# H15R80.net
KiCad netlist of a schematic drawn in EAGLE
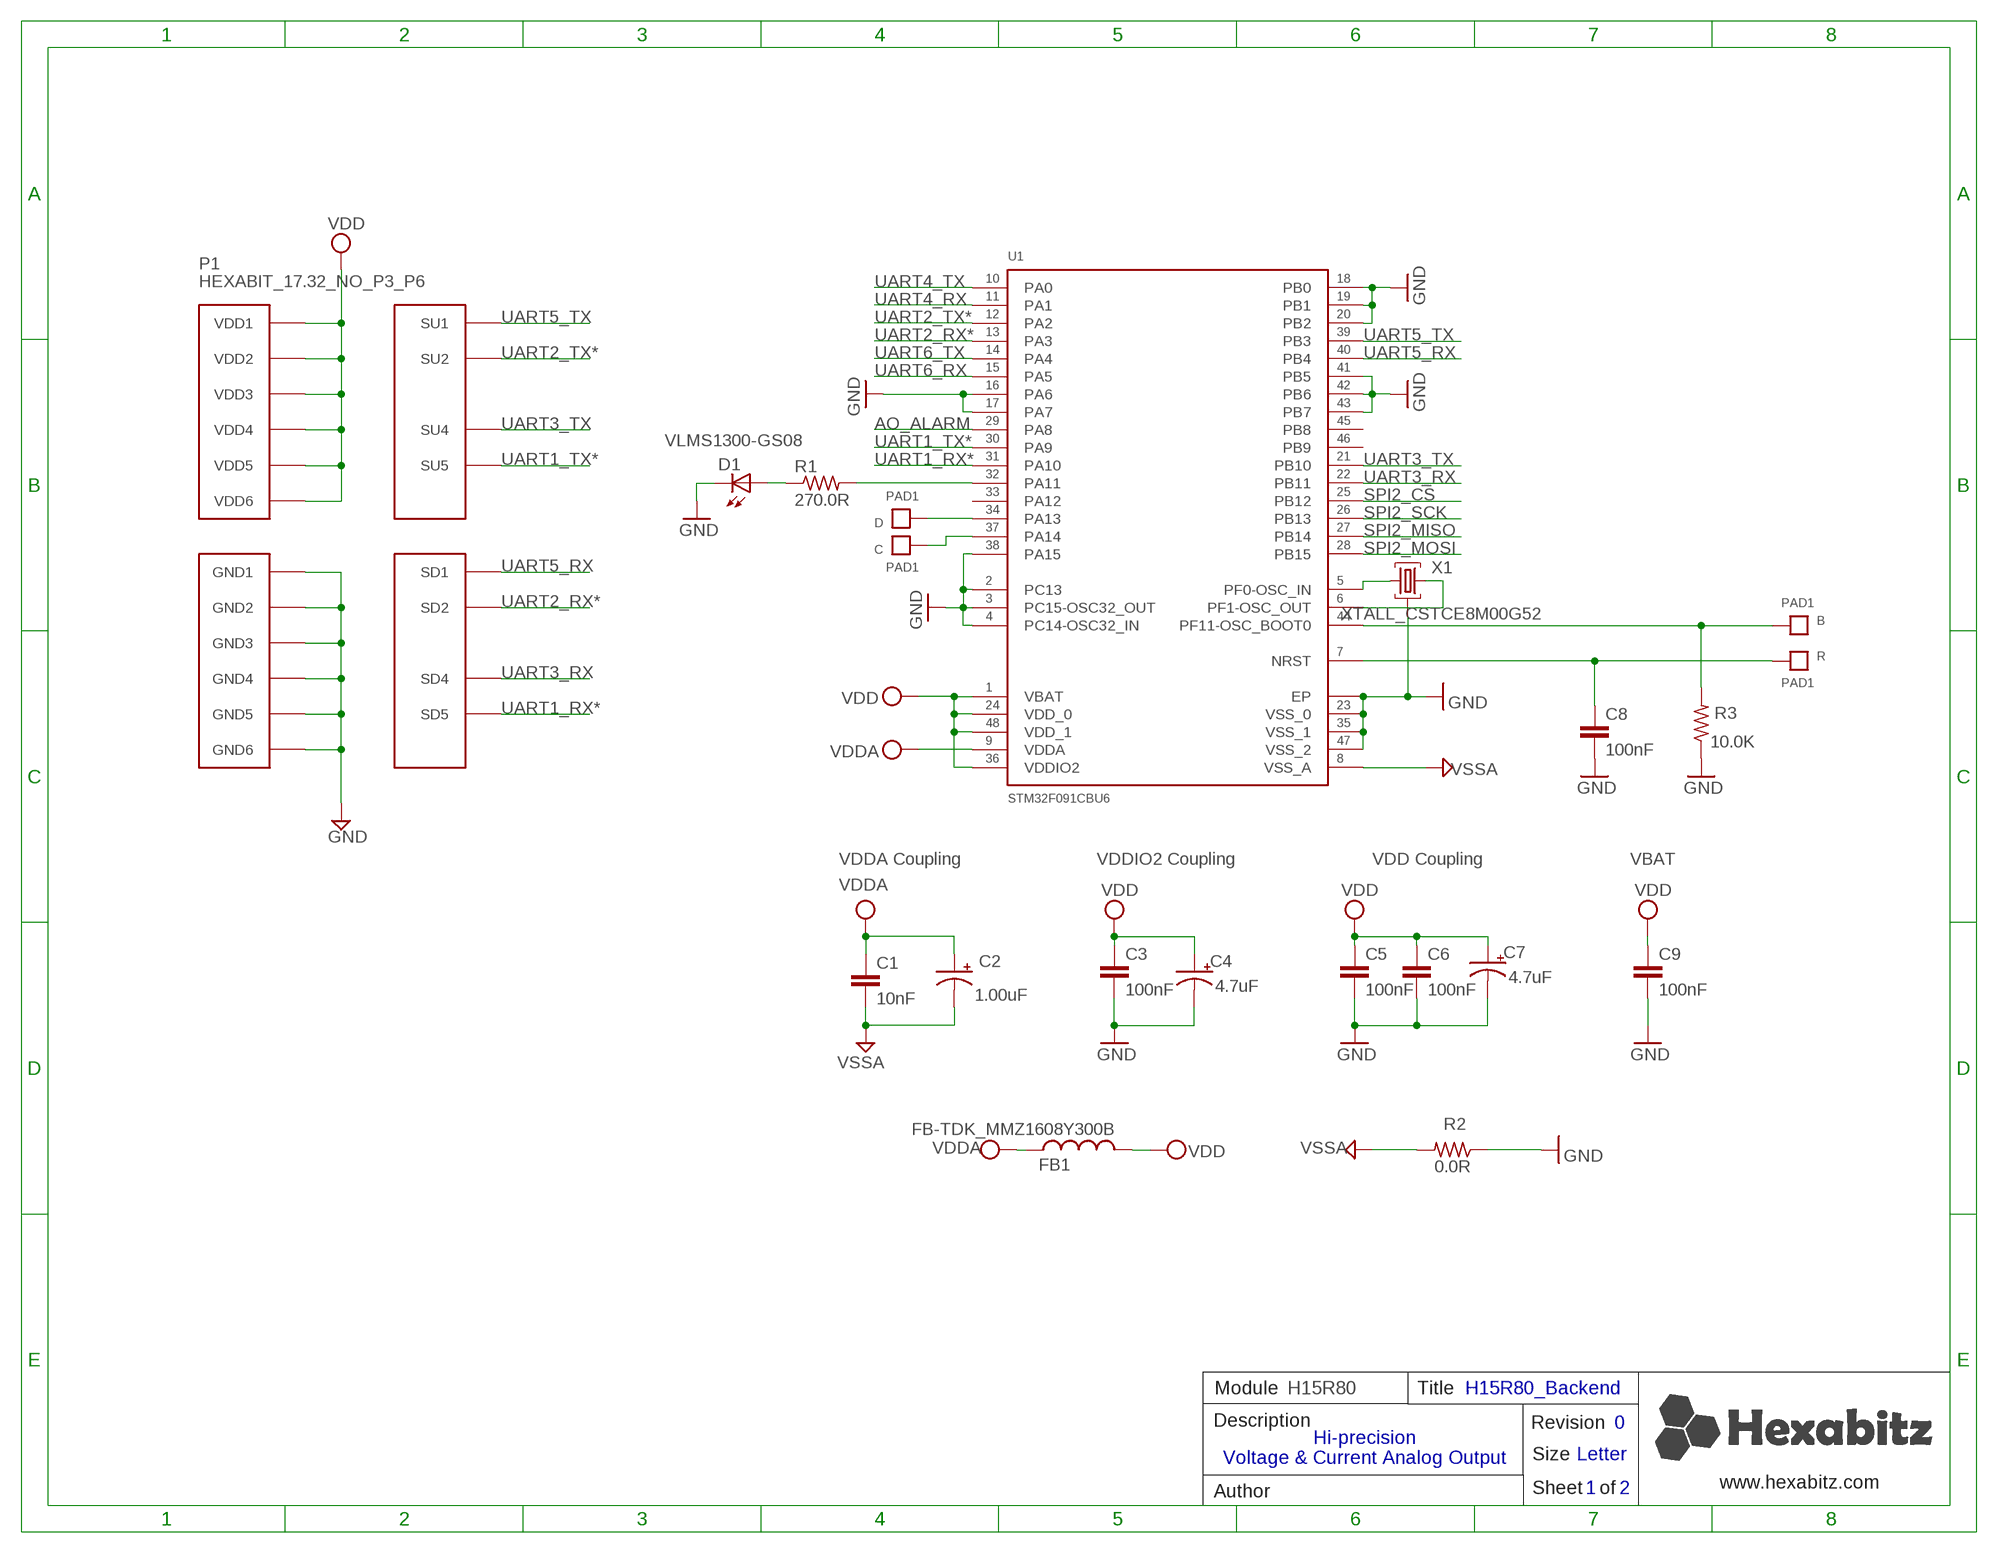
[diagram p0: schematic, sheet 1]
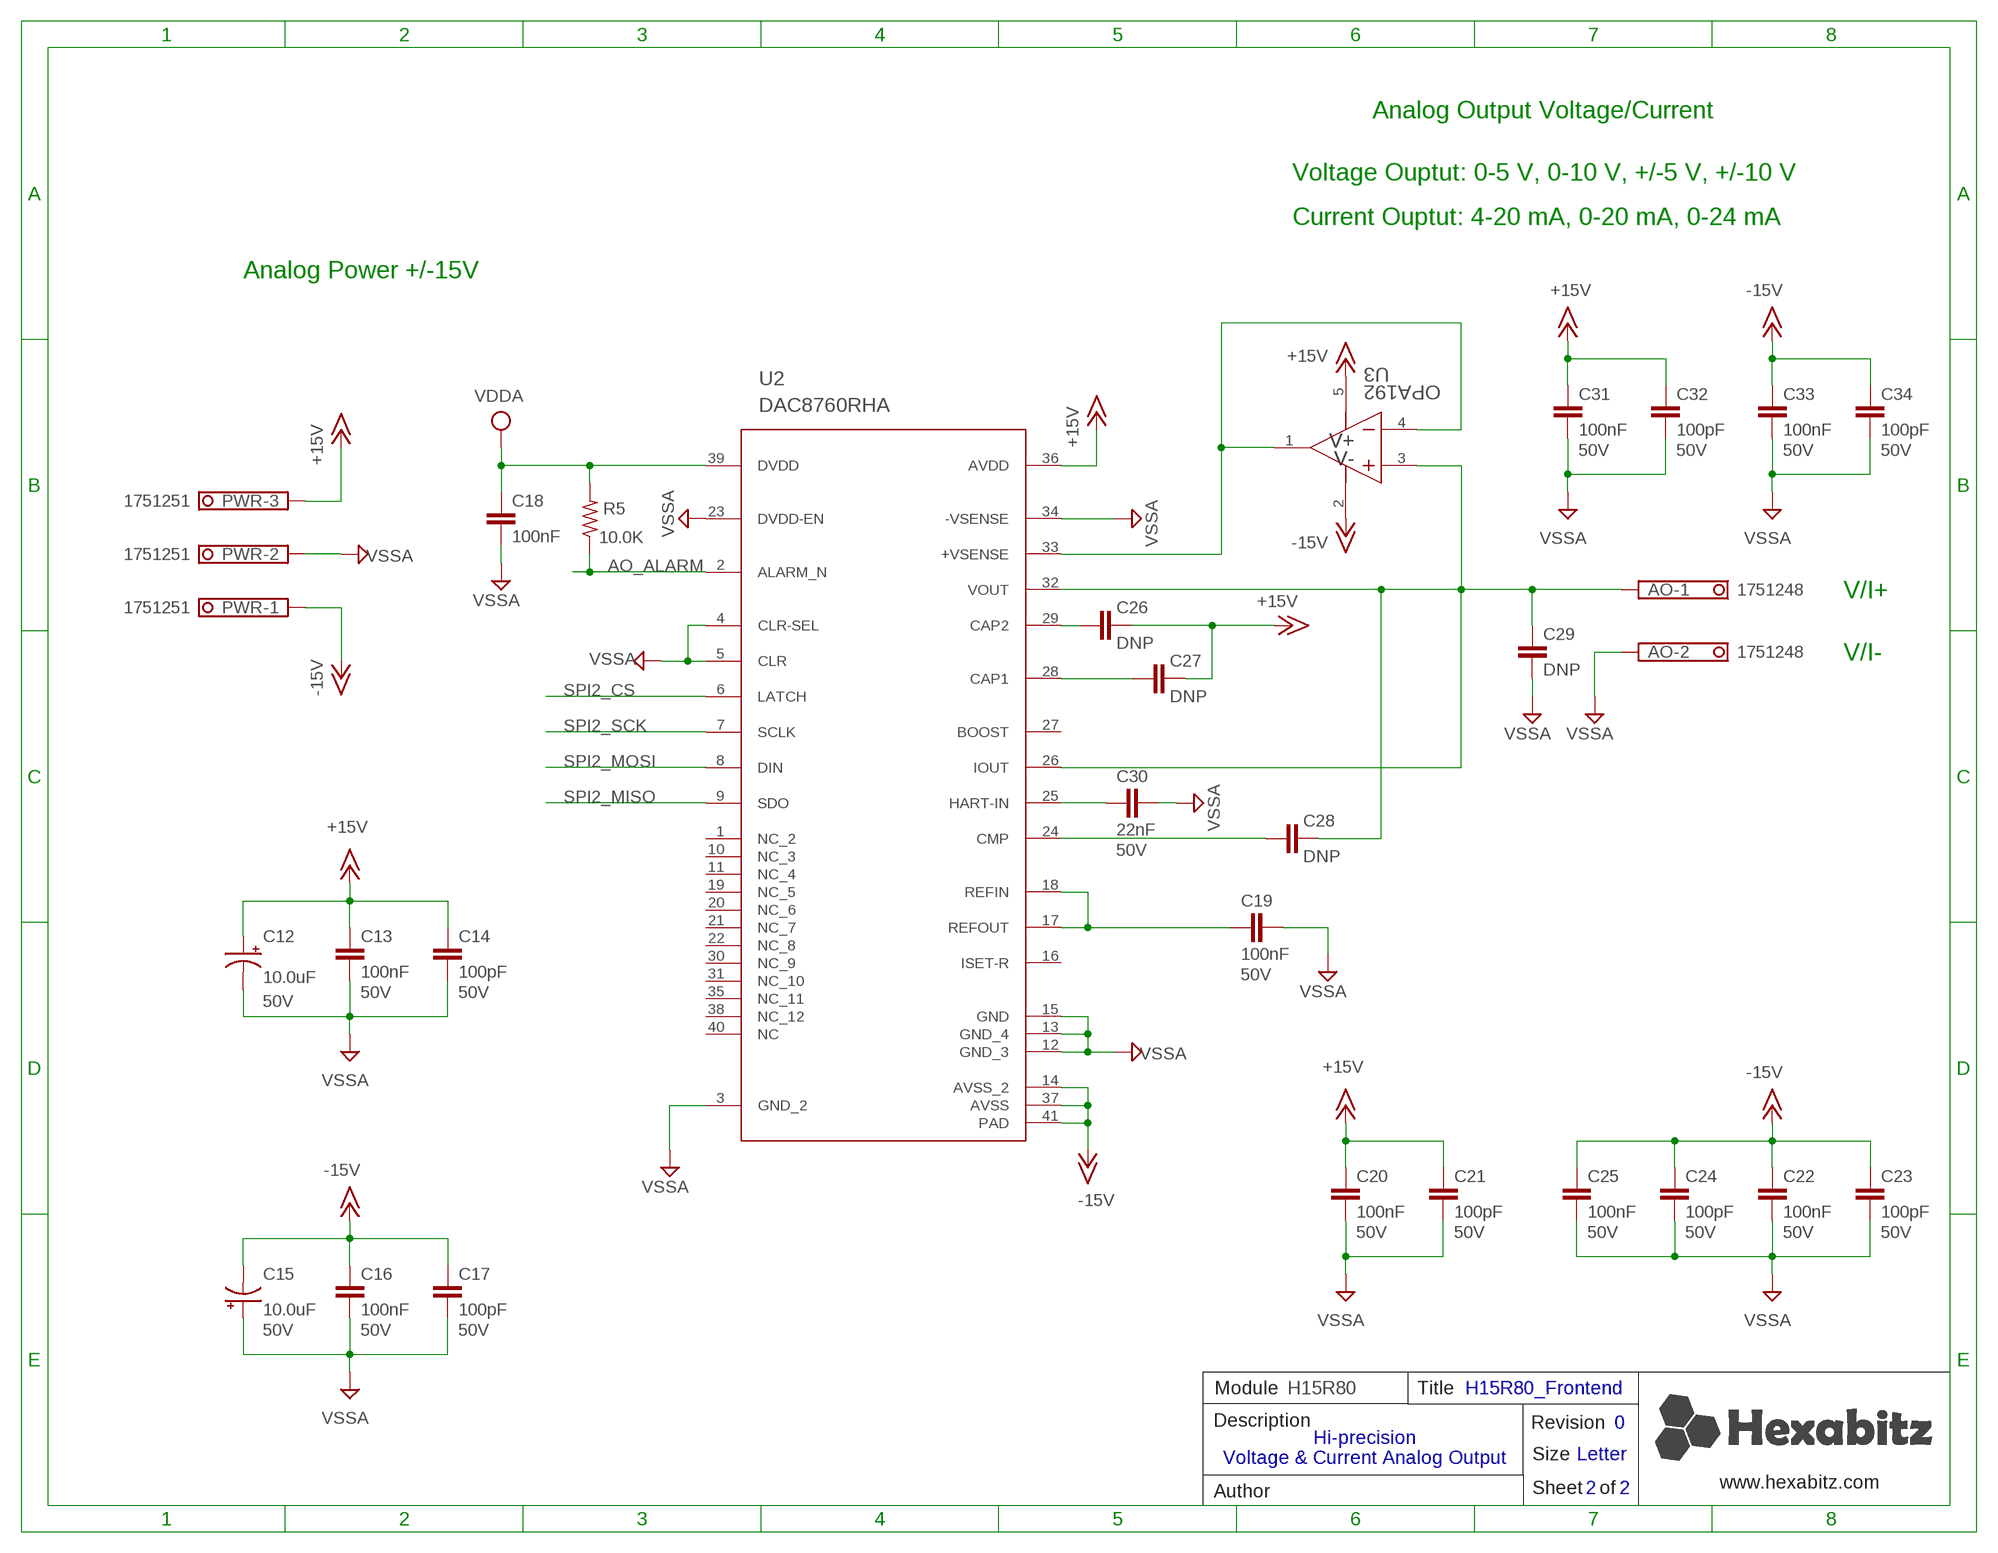
[diagram p1: schematic, sheet 2]

(export (version "E")
  (design (tool "Eeschema 10.0.6"))
  (components
    (comp (ref "B")
      (value "PAD1")
      (footprint "eagle-import:PAD1")
      (libsource (lib "eagle-import") (part "PAD1"))
    )
    (comp (ref "C")
      (value "PAD1")
      (footprint "eagle-import:PAD1")
      (libsource (lib "eagle-import") (part "PAD1"))
    )
    (comp (ref "C1")
      (value "10nF")
      (footprint "eagle-import:C-0603")
      (fields
        (field (name "CAPACITANCE") "10nF")
        (field (name "MFN") "KEMET")
        (field (name "MPN") "C0603C103K5RACTU")
        (field (name "OCTOPART_URL") "https://octopart.com/c0603c103k5ractu-kemet-133094?r=sp&s=R_iPBxLnSmGqhkU2rIMFpg")
        (field (name "TOLERANCE") "10%")
        (field (name "VOLTAGE_RATING") "50V")
      )
      (libsource (lib "eagle-import") (part "C-0603"))
    )
    (comp (ref "C2")
      (value "1.00uF")
      (footprint "eagle-import:C-0805-POL")
      (fields
        (field (name "CAPACITANCE") "1.00uF")
        (field (name "MFN") "Yageo")
        (field (name "MPN") "CC0805KKX7R7BB105")
        (field (name "OCTOPART_URL") "https://octopart.com/cc0805kkx7r7bb105-yageo-8376555?r=sp&s=YKl1wwtkROau_X5nniH2ig")
        (field (name "TOLERANCE") "10%")
        (field (name "VOLTAGE_RATING") "16V")
      )
      (libsource (lib "eagle-import") (part "C-0805-POL"))
    )
    (comp (ref "C3")
      (value "100nF")
      (footprint "eagle-import:C-0603")
      (fields
        (field (name "CAPACITANCE") "100nF")
        (field (name "MFN") "KEMET")
        (field (name "MPN") "C0603C104K8RACTU")
        (field (name "OCTOPART_URL") "https://octopart.com/c0603c104k8ractu-kemet-145075?r=sp&s=9bS9ASSwSEqMCE9KBEQZ0g")
        (field (name "TOLERANCE") "10%")
        (field (name "VOLTAGE_RATING") "10V")
      )
      (libsource (lib "eagle-import") (part "C-0603"))
    )
    (comp (ref "C4")
      (value "4.7uF")
      (footprint "eagle-import:C-0805-POL")
      (fields
        (field (name "CAPACITANCE") "4.7uF")
        (field (name "MFN") "Murata")
        (field (name "MPN") "GRM21BC81E475KA12L")
        (field (name "OCTOPART_URL") "https://octopart.com/grm21bc81e475ka12l-murata-10331911?r=sp&s=RY3qZSD8T6mG6TC9CHI5qQ")
        (field (name "TOLERANCE") "10%")
        (field (name "VOLTAGE_RATING") "25V")
      )
      (libsource (lib "eagle-import") (part "C-0805-POL"))
    )
    (comp (ref "C5")
      (value "100nF")
      (footprint "eagle-import:C-0603")
      (fields
        (field (name "CAPACITANCE") "100nF")
        (field (name "MFN") "KEMET")
        (field (name "MPN") "C0603C104K8RACTU")
        (field (name "OCTOPART_URL") "https://octopart.com/c0603c104k8ractu-kemet-145075?r=sp&s=9bS9ASSwSEqMCE9KBEQZ0g")
        (field (name "TOLERANCE") "10%")
        (field (name "VOLTAGE_RATING") "10")
      )
      (libsource (lib "eagle-import") (part "C-0603"))
    )
    (comp (ref "C6")
      (value "100nF")
      (footprint "eagle-import:C-0603")
      (fields
        (field (name "CAPACITANCE") "100nF")
        (field (name "MFN") "KEMET")
        (field (name "MPN") "C0603C104K8RACTU")
        (field (name "OCTOPART_URL") "https://octopart.com/c0603c104k8ractu-kemet-145075?r=sp&s=9bS9ASSwSEqMCE9KBEQZ0g")
        (field (name "TOLERANCE") "10%")
        (field (name "VOLTAGE_RATING") "10V")
      )
      (libsource (lib "eagle-import") (part "C-0603"))
    )
    (comp (ref "C7")
      (value "4.7uF")
      (footprint "eagle-import:C-0805-POL")
      (fields
        (field (name "CAPACITANCE") "4.7uF")
        (field (name "MFN") "Murata")
        (field (name "MPN") "GRM21BC81E475KA12L")
        (field (name "OCTOPART_URL") "https://octopart.com/grm21bc81e475ka12l-murata-10331911?r=sp&s=RY3qZSD8T6mG6TC9CHI5qQ")
        (field (name "TOLERANCE") "10%")
        (field (name "VOLTAGE_RATING") "25V")
      )
      (libsource (lib "eagle-import") (part "C-0805-POL"))
    )
    (comp (ref "C8")
      (value "100nF")
      (footprint "eagle-import:C-0603")
      (fields
        (field (name "CAPACITANCE") "100nF")
        (field (name "MFN") "KEMET")
        (field (name "MPN") "C0603C104K8RACTU")
        (field (name "OCTOPART_URL") "https://octopart.com/c0603c104k8ractu-kemet-145075?r=sp&s=9bS9ASSwSEqMCE9KBEQZ0g")
        (field (name "TOLERANCE") "10%")
        (field (name "VOLTAGE_RATING") "10V")
      )
      (libsource (lib "eagle-import") (part "C-0603"))
    )
    (comp (ref "C9")
      (value "100nF")
      (footprint "eagle-import:C-0603")
      (fields
        (field (name "CAPACITANCE") "100nF")
        (field (name "MFN") "KEMET")
        (field (name "MPN") "C0603C104K8RACTU")
        (field (name "OCTOPART_URL") "https://octopart.com/c0603c104k8ractu-kemet-145075?r=sp&s=9bS9ASSwSEqMCE9KBEQZ0g")
        (field (name "TOLERANCE") "10V")
        (field (name "VOLTAGE_RATING") "10%")
      )
      (libsource (lib "eagle-import") (part "C-0603"))
    )
    (comp (ref "D")
      (value "PAD1")
      (footprint "eagle-import:PAD1")
      (libsource (lib "eagle-import") (part "PAD1"))
    )
    (comp (ref "D1")
      (value "VLMS1300-GS08")
      (footprint "eagle-import:VLMS1300-GS08")
      (fields
        (field (name "MFN") "Vishay")
        (field (name "MPN") "VLMS1300-GS08")
        (field (name "OCTOPART_URL") "https://octopart.com/vlms1300-gs08-vishay-21709201?r=sp&s=_gcP4_q8T1SC6PJQPTQ9yA")
      )
      (libsource (lib "eagle-import") (part "VLMS1300-GS08"))
    )
    (comp (ref "FB1")
      (value "FB-TDK_MMZ1608Y300B")
      (footprint "eagle-import:FB-TDK_MMZ1608Y300B")
      (fields
        (field (name "MFN") "TDK ")
        (field (name "MPN") "MMZ1608Y300B")
        (field (name "OCTOPART_URL") "https://octopart.com/mmz1608y300b-tdk-368280?r=sp&s=cd9_2ZEqQ9q9UNBuQgHAiA")
      )
      (libsource (lib "eagle-import") (part "FB-TDK_MMZ1608Y300B"))
    )
    (comp (ref "P1")
      (value "HEXABIT_17.32_NO_P3_P6")
      (footprint "eagle-import:HEXABIT_17.32_NO_P3_P6")
      (libsource (lib "eagle-import") (part "HEXABIT_?_NO_P3_P617.32"))
    )
    (comp (ref "R")
      (value "PAD1")
      (footprint "eagle-import:PAD1")
      (libsource (lib "eagle-import") (part "PAD1"))
    )
    (comp (ref "R1")
      (value "270.0R")
      (footprint "eagle-import:R-0603")
      (fields
        (field (name "MFN") "Yageo")
        (field (name "MPN") "RC0603FR-07270RL")
        (field (name "OCTOPART_URL") "https://octopart.com/search?q=RC0603FR-07270RL&start=0")
        (field (name "RESISTANCE") "270.0 Ohm")
        (field (name "TOLERANCE") "1%")
      )
      (libsource (lib "eagle-import") (part "R-0603"))
    )
    (comp (ref "R2")
      (value "0.0R")
      (footprint "eagle-import:R-0603")
      (fields
        (field (name "MFN") "Yageo")
        (field (name "MPN") "RC0603JR-070RL")
        (field (name "OCTOPART_URL") "https://octopart.com/rc0603jr-070rl-yageo-1241539?r=sp&s=X2NteqRjRNWrnx42Y0aliA")
        (field (name "RESISTANCE") "0.0 Ohm")
      )
      (libsource (lib "eagle-import") (part "R-0603"))
    )
    (comp (ref "R3")
      (value "10.0K")
      (footprint "eagle-import:R-0603")
      (fields
        (field (name "MFN") "Yageo")
        (field (name "MPN") "RC0603JR-0710KL")
        (field (name "OCTOPART_URL") "https://octopart.com/search?q=RC0603JR-0710KL&start=0")
        (field (name "RESISTANCE") "10.0K Ohm")
        (field (name "TOLERANCE") "5%")
      )
      (libsource (lib "eagle-import") (part "R-0603"))
    )
    (comp (ref "U1")
      (value "STM32F091CBU6")
      (footprint "eagle-import:STM32F091CBU6")
      (libsource (lib "eagle-import") (part "STM32F091CBU6"))
    )
    (comp (ref "X1")
      (value "XTALL_CSTCE8M00G52")
      (footprint "eagle-import:XTALL_CSTCE8M00G52")
      (fields (field (name "MPN") "CSTCE8M00G52Z-R0"))
      (libsource (lib "eagle-import") (part "XTALL_CSTCE8M00G52"))
    )
    (comp (ref "AO")
      (value "1751248")
      (footprint "eagle-import:1751248")
      (fields
        (field (name "MPN") "1751248")
        (field (name "MFN") "Phoenix Contact")
        (field (name "OCTOPART_URL") "https://octopart.com/1751248-phoenix+contact-31334?r=sp&s=dfbEyNHiQNetUL69ahOrPQ ")
      )
      (libsource (lib "eagle-import") (part "1751248"))
    )
    (comp (ref "C12")
      (value "10.0uF")
      (footprint "eagle-import:CT7343")
      (fields (field (name "MPN") "T491D106K050AT") (field (name "VOLTAGE") "50V"))
      (libsource (lib "eagle-import") (part "CPOL-USCT7343"))
    )
    (comp (ref "C13")
      (value "100nF")
      (footprint "eagle-import:C-0603")
      (fields
        (field (name "CAPACITANCE") "100nF")
        (field (name "MFN") "Samsung")
        (field (name "MPN") "CL10B104KB8NNNC")
        (field (name "OCTOPART_URL") "https://octopart.com/cl10b104kb8nnnc-samsung-7928277?r=sp&s=fIKkgin8S22eXTUxF1gXsw")
        (field (name "TOLERANCE") "10%")
        (field (name "VOLTAGE_RATING") "50V")
      )
      (libsource (lib "eagle-import") (part "C-0603"))
    )
    (comp (ref "C14")
      (value "100pF")
      (footprint "eagle-import:C-0603")
      (fields
        (field (name "CAPACITANCE") "100pF")
        (field (name "MFN") "Avx")
        (field (name "MPN") "06035A101JAT2A")
        (field (name "OCTOPART_URL") "https://octopart.com/06035a101jat2a-avx-55386344?r=sp&s=WDfgRo-ITV2A4U5JT5ZyKQ")
        (field (name "TOLERANCE") "10%")
        (field (name "VOLTAGE_RATING") "50V")
      )
      (libsource (lib "eagle-import") (part "C-0603"))
    )
    (comp (ref "C15")
      (value "10.0uF")
      (footprint "eagle-import:CT7343")
      (fields (field (name "MPN") "T491D106K050AT") (field (name "VOLTAGE") "50V"))
      (libsource (lib "eagle-import") (part "CPOL-USCT7343"))
    )
    (comp (ref "C16")
      (value "100nF")
      (footprint "eagle-import:C-0603")
      (fields
        (field (name "CAPACITANCE") "100nF")
        (field (name "MFN") "Samsung")
        (field (name "MPN") "CL10B104KB8NNNC")
        (field (name "OCTOPART_URL") "https://octopart.com/cl10b104kb8nnnc-samsung-7928277?r=sp&s=fIKkgin8S22eXTUxF1gXsw")
        (field (name "TOLERANCE") "10%")
        (field (name "VOLTAGE_RATING") "50V")
      )
      (libsource (lib "eagle-import") (part "C-0603"))
    )
    (comp (ref "C17")
      (value "100pF")
      (footprint "eagle-import:C-0603")
      (fields
        (field (name "CAPACITANCE") "100pF")
        (field (name "MFN") "Avx")
        (field (name "MPN") "06035A101JAT2A")
        (field (name "OCTOPART_URL") "https://octopart.com/06035a101jat2a-avx-55386344?r=sp&s=WDfgRo-ITV2A4U5JT5ZyKQ")
        (field (name "TOLERANCE") "10%")
        (field (name "VOLTAGE_RATING") "50V")
      )
      (libsource (lib "eagle-import") (part "C-0603"))
    )
    (comp (ref "C18")
      (value "100nF")
      (footprint "eagle-import:C-0603")
      (fields
        (field (name "CAPACITANCE") "100nF")
        (field (name "MFN") "KEMET")
        (field (name "MPN") "C0603C104K8RACTU")
        (field (name "OCTOPART_URL") "https://octopart.com/c0603c104k8ractu-kemet-145075?r=sp&s=9bS9ASSwSEqMCE9KBEQZ0g")
        (field (name "TOLERANCE") "10%")
        (field (name "VOLTAGE_RATING") "10V")
      )
      (libsource (lib "eagle-import") (part "C-0603"))
    )
    (comp (ref "C19")
      (value "100nF")
      (footprint "eagle-import:C-0603")
      (fields
        (field (name "CAPACITANCE") "100nF")
        (field (name "MFN") "Samsung")
        (field (name "MPN") "CL10B104KB8NNNC")
        (field (name "OCTOPART_URL") "https://octopart.com/cl10b104kb8nnnc-samsung-7928277?r=sp&s=fIKkgin8S22eXTUxF1gXsw")
        (field (name "TOLERANCE") "10%")
        (field (name "VOLTAGE_RATING") "50V")
      )
      (libsource (lib "eagle-import") (part "C-0603"))
    )
    (comp (ref "C20")
      (value "100nF")
      (footprint "eagle-import:C-0603")
      (fields
        (field (name "CAPACITANCE") "100nF")
        (field (name "MFN") "Samsung")
        (field (name "MPN") "CL10B104KB8NNNC")
        (field (name "OCTOPART_URL") "https://octopart.com/cl10b104kb8nnnc-samsung-7928277?r=sp&s=fIKkgin8S22eXTUxF1gXsw")
        (field (name "TOLERANCE") "10%")
        (field (name "VOLTAGE_RATING") "50V")
      )
      (libsource (lib "eagle-import") (part "C-0603"))
    )
    (comp (ref "C21")
      (value "100pF")
      (footprint "eagle-import:C-0603")
      (fields
        (field (name "CAPACITANCE") "100pF")
        (field (name "MFN") "Avx")
        (field (name "MPN") "06035A101JAT2A")
        (field (name "OCTOPART_URL") "https://octopart.com/06035a101jat2a-avx-55386344?r=sp&s=WDfgRo-ITV2A4U5JT5ZyKQ")
        (field (name "TOLERANCE") "10%")
        (field (name "VOLTAGE_RATING") "50V")
      )
      (libsource (lib "eagle-import") (part "C-0603"))
    )
    (comp (ref "C22")
      (value "100nF")
      (footprint "eagle-import:C-0603")
      (fields
        (field (name "CAPACITANCE") "100nF")
        (field (name "MFN") "Samsung")
        (field (name "MPN") "CL10B104KB8NNNC")
        (field (name "OCTOPART_URL") "https://octopart.com/cl10b104kb8nnnc-samsung-7928277?r=sp&s=fIKkgin8S22eXTUxF1gXsw")
        (field (name "TOLERANCE") "10%")
        (field (name "VOLTAGE_RATING") "50V")
      )
      (libsource (lib "eagle-import") (part "C-0603"))
    )
    (comp (ref "C23")
      (value "100pF")
      (footprint "eagle-import:C-0603")
      (fields
        (field (name "CAPACITANCE") "100pF")
        (field (name "MFN") "Avx")
        (field (name "MPN") "06035A101JAT2A")
        (field (name "OCTOPART_URL") "https://octopart.com/06035a101jat2a-avx-55386344?r=sp&s=WDfgRo-ITV2A4U5JT5ZyKQ")
        (field (name "TOLERANCE") "10%")
        (field (name "VOLTAGE_RATING") "50V")
      )
      (libsource (lib "eagle-import") (part "C-0603"))
    )
    (comp (ref "C24")
      (value "100pF")
      (footprint "eagle-import:C-0603")
      (fields
        (field (name "CAPACITANCE") "100pF")
        (field (name "MFN") "Avx")
        (field (name "MPN") "06035A101JAT2A")
        (field (name "OCTOPART_URL") "https://octopart.com/06035a101jat2a-avx-55386344?r=sp&s=WDfgRo-ITV2A4U5JT5ZyKQ")
        (field (name "TOLERANCE") "10%")
        (field (name "VOLTAGE_RATING") "50V")
      )
      (libsource (lib "eagle-import") (part "C-0603"))
    )
    (comp (ref "C25")
      (value "100nF")
      (footprint "eagle-import:C-0603")
      (fields
        (field (name "CAPACITANCE") "100nF")
        (field (name "MFN") "Samsung")
        (field (name "MPN") "CL10B104KB8NNNC")
        (field (name "OCTOPART_URL") "https://octopart.com/cl10b104kb8nnnc-samsung-7928277?r=sp&s=fIKkgin8S22eXTUxF1gXsw")
        (field (name "TOLERANCE") "10%")
        (field (name "VOLTAGE_RATING") "50V")
      )
      (libsource (lib "eagle-import") (part "C-0603"))
    )
    (comp (ref "C26")
      (value "DNP")
      (footprint "eagle-import:C-0603")
      (fields (field (name "CAPACITANCE") "DNP") (field (name "MPN") "DNP"))
      (libsource (lib "eagle-import") (part "C-0603"))
    )
    (comp (ref "C27")
      (value "DNP")
      (footprint "eagle-import:C-0603")
      (fields (field (name "CAPACITANCE") "DNP") (field (name "MPN") "DNP"))
      (libsource (lib "eagle-import") (part "C-0603"))
    )
    (comp (ref "C28")
      (value "DNP")
      (footprint "eagle-import:C-0603")
      (fields (field (name "CAPACITANCE") "DNP") (field (name "MPN") "DNP"))
      (libsource (lib "eagle-import") (part "C-0603"))
    )
    (comp (ref "C29")
      (value "DNP")
      (footprint "eagle-import:C-0603")
      (fields (field (name "CAPACITANCE") "DNP") (field (name "MPN") "DNP"))
      (libsource (lib "eagle-import") (part "C-0603"))
    )
    (comp (ref "C30")
      (value "22nF")
      (footprint "eagle-import:C-0603")
      (fields
        (field (name "CAPACITANCE") "22nF")
        (field (name "MFN") "TDK")
        (field (name "MPN") "C1608X7R1H223K080AA")
        (field (name "OCTOPART_URL") "https://octopart.com/c1608x7r1h223k080aa-tdk-25947667?r=sp&s=T8cT_uRxS7ewuHBmxCxszg")
        (field (name "TOLERANCE") "10%")
        (field (name "VOLTAGE_RATING") "50V")
      )
      (libsource (lib "eagle-import") (part "C-0603"))
    )
    (comp (ref "C31")
      (value "100nF")
      (footprint "eagle-import:C-0603")
      (fields
        (field (name "CAPACITANCE") "100nF")
        (field (name "MFN") "Samsung")
        (field (name "MPN") "CL10B104KB8NNNC")
        (field (name "OCTOPART_URL") "https://octopart.com/cl10b104kb8nnnc-samsung-7928277?r=sp&s=fIKkgin8S22eXTUxF1gXsw")
        (field (name "TOLERANCE") "10%")
        (field (name "VOLTAGE_RATING") "50V")
      )
      (libsource (lib "eagle-import") (part "C-0603"))
    )
    (comp (ref "C32")
      (value "100pF")
      (footprint "eagle-import:C-0603")
      (fields
        (field (name "CAPACITANCE") "100pF")
        (field (name "MFN") "Avx")
        (field (name "MPN") "06035A101JAT2A")
        (field (name "OCTOPART_URL") "https://octopart.com/06035a101jat2a-avx-55386344?r=sp&s=WDfgRo-ITV2A4U5JT5ZyKQ")
        (field (name "TOLERANCE") "10%")
        (field (name "VOLTAGE_RATING") "50V")
      )
      (libsource (lib "eagle-import") (part "C-0603"))
    )
    (comp (ref "C33")
      (value "100nF")
      (footprint "eagle-import:C-0603")
      (fields
        (field (name "CAPACITANCE") "100nF")
        (field (name "MFN") "Samsung")
        (field (name "MPN") "CL10B104KB8NNNC")
        (field (name "OCTOPART_URL") "https://octopart.com/cl10b104kb8nnnc-samsung-7928277?r=sp&s=fIKkgin8S22eXTUxF1gXsw")
        (field (name "TOLERANCE") "10%")
        (field (name "VOLTAGE_RATING") "50V")
      )
      (libsource (lib "eagle-import") (part "C-0603"))
    )
    (comp (ref "C34")
      (value "100pF")
      (footprint "eagle-import:C-0603")
      (fields
        (field (name "CAPACITANCE") "100pF")
        (field (name "MFN") "Avx")
        (field (name "MPN") "06035A101JAT2A")
        (field (name "OCTOPART_URL") "https://octopart.com/06035a101jat2a-avx-55386344?r=sp&s=WDfgRo-ITV2A4U5JT5ZyKQ")
        (field (name "TOLERANCE") "10%")
        (field (name "VOLTAGE_RATING") "50V")
      )
      (libsource (lib "eagle-import") (part "C-0603"))
    )
    (comp (ref "PWR")
      (value "1751251")
      (footprint "eagle-import:1751251")
      (fields
        (field (name "MFN") "Phoenix Contact")
        (field (name "MPN") "1751251")
        (field (name "OCTOPART_URL") "https://octopart.com/1751251-phoenix+contact-36473?r=sp&s=9M0VWNoHTyq04j3qI6lQOQ ")
      )
      (libsource (lib "eagle-import") (part "1751251"))
    )
    (comp (ref "R5")
      (value "10.0K")
      (footprint "eagle-import:R-0603")
      (fields
        (field (name "MFN") "Yageo")
        (field (name "MPN") "RC0603JR-0710KL")
        (field (name "OCTOPART_URL") "https://octopart.com/search?q=RC0603JR-0710KL&start=0")
        (field (name "RESISTANCE") "10.0K Ohm")
        (field (name "TOLERANCE") "5%")
      )
      (libsource (lib "eagle-import") (part "R-0603"))
    )
    (comp (ref "U2")
      (value "DAC8760RHA")
      (footprint "eagle-import:RHA0040A")
      (fields
        (field (name "MANUFACTURER") "Texas Instruments")
        (field (name "MPN") "DAC8760IRHAR")
        (field (name "PARTNUMBER") "DAC7760IRHAR")
      )
      (libsource (lib "eagle-import") (part "DAC7760IRHAR"))
    )
    (comp (ref "U3")
      (value "OPA192")
      (footprint "eagle-import:DBV0005A_N")
      (fields
        (field (name "ALTERNATE_PARTNUMBER") "OPA192IDBVT")
        (field (name "MANUFACTURER") "Texas Instruments")
        (field (name "PARTNUMBER") "OPA192IDBVR")
      )
      (libsource (lib "eagle-import") (part "OPA192IDBVR"))
    )
  )
  (nets
    (net (code "1") (name "+15V") (class "Default")
      (node (ref "C12") (pin "+") (pinfunction "+_+") (pintype "passive"))
      (node (ref "C13") (pin "1") (pinfunction "1_1") (pintype "passive"))
      (node (ref "C14") (pin "1") (pinfunction "1_1") (pintype "passive"))
      (node (ref "C20") (pin "1") (pinfunction "1_1") (pintype "passive"))
      (node (ref "C21") (pin "1") (pinfunction "1_1") (pintype "passive"))
      (node (ref "C26") (pin "2") (pinfunction "2_2") (pintype "passive"))
      (node (ref "C27") (pin "2") (pinfunction "2_2") (pintype "passive"))
      (node (ref "C31") (pin "1") (pinfunction "1_1") (pintype "passive"))
      (node (ref "C32") (pin "1") (pinfunction "1_1") (pintype "passive"))
      (node (ref "PWR") (pin "3") (pinfunction "K_3") (pintype "passive"))
      (node (ref "U2") (pin "36") (pinfunction "AVDD_36") (pintype "power_in"))
      (node (ref "U3") (pin "5") (pinfunction "V+_5") (pintype "power_in"))
    )
    (net (code "2") (name "-15V") (class "Default")
      (node (ref "C15") (pin "-") (pinfunction "-_-") (pintype "passive"))
      (node (ref "C16") (pin "1") (pinfunction "1_1") (pintype "passive"))
      (node (ref "C17") (pin "1") (pinfunction "1_1") (pintype "passive"))
      (node (ref "C22") (pin "1") (pinfunction "1_1") (pintype "passive"))
      (node (ref "C23") (pin "1") (pinfunction "1_1") (pintype "passive"))
      (node (ref "C24") (pin "1") (pinfunction "1_1") (pintype "passive"))
      (node (ref "C25") (pin "1") (pinfunction "1_1") (pintype "passive"))
      (node (ref "C33") (pin "1") (pinfunction "1_1") (pintype "passive"))
      (node (ref "C34") (pin "1") (pinfunction "1_1") (pintype "passive"))
      (node (ref "PWR") (pin "1") (pinfunction "K_1") (pintype "passive"))
      (node (ref "U2") (pin "14") (pinfunction "AVSS_2_14") (pintype "power_in"))
      (node (ref "U2") (pin "37") (pinfunction "AVSS_37") (pintype "power_in"))
      (node (ref "U2") (pin "41") (pinfunction "PAD_41") (pintype "power_in"))
      (node (ref "U3") (pin "2") (pinfunction "V-_2") (pintype "power_in"))
    )
    (net (code "3") (name "AO_ALARM") (class "Default")
      (node (ref "R5") (pin "1") (pinfunction "1_1") (pintype "passive"))
      (node (ref "U1") (pin "P$29") (pinfunction "PA8_P$29") (pintype "bidirectional"))
      (node (ref "U2") (pin "2") (pinfunction "ALARM_N_2") (pintype "open_collector"))
    )
    (net (code "4") (name "GND") (class "Default")
      (node (ref "C3") (pin "2") (pinfunction "2_2") (pintype "passive"))
      (node (ref "C4") (pin "2") (pinfunction "-_2") (pintype "passive"))
      (node (ref "C5") (pin "2") (pinfunction "2_2") (pintype "passive"))
      (node (ref "C6") (pin "2") (pinfunction "2_2") (pintype "passive"))
      (node (ref "C7") (pin "2") (pinfunction "-_2") (pintype "passive"))
      (node (ref "C8") (pin "2") (pinfunction "2_2") (pintype "passive"))
      (node (ref "C9") (pin "2") (pinfunction "2_2") (pintype "passive"))
      (node (ref "D1") (pin "C") (pinfunction "C_C") (pintype "passive"))
      (node (ref "P1") (pin "PAD_PD10") (pinfunction "GND4_PAD_PD10") (pintype "power_in"))
      (node (ref "P1") (pin "PAD_PD11") (pinfunction "GND5_PAD_PD11") (pintype "power_in"))
      (node (ref "P1") (pin "PAD_PD12") (pinfunction "GND6_PAD_PD12") (pintype "power_in"))
      (node (ref "P1") (pin "PAD_PD7") (pinfunction "GND1_PAD_PD7") (pintype "power_in"))
      (node (ref "P1") (pin "PAD_PD8") (pinfunction "GND2_PAD_PD8") (pintype "power_in"))
      (node (ref "P1") (pin "PAD_PD9") (pinfunction "GND3_PAD_PD9") (pintype "power_in"))
      (node (ref "R2") (pin "1") (pinfunction "1_1") (pintype "passive"))
      (node (ref "R3") (pin "1") (pinfunction "1_1") (pintype "passive"))
      (node (ref "U1") (pin "EP") (pinfunction "EP_EP") (pintype "power_in"))
      (node (ref "U1") (pin "P$16") (pinfunction "PA6_P$16") (pintype "bidirectional"))
      (node (ref "U1") (pin "P$17") (pinfunction "PA7_P$17") (pintype "bidirectional"))
      (node (ref "U1") (pin "P$18") (pinfunction "PB0_P$18") (pintype "bidirectional"))
      (node (ref "U1") (pin "P$19") (pinfunction "PB1_P$19") (pintype "bidirectional"))
      (node (ref "U1") (pin "P$2") (pinfunction "PC13_P$2") (pintype "bidirectional"))
      (node (ref "U1") (pin "P$20") (pinfunction "PB2_P$20") (pintype "bidirectional"))
      (node (ref "U1") (pin "P$23") (pinfunction "VSS_0_P$23") (pintype "power_in"))
      (node (ref "U1") (pin "P$3") (pinfunction "PC14-OSC32_IN_P$3") (pintype "bidirectional"))
      (node (ref "U1") (pin "P$35") (pinfunction "VSS_1_P$35") (pintype "power_in"))
      (node (ref "U1") (pin "P$38") (pinfunction "PA15_P$38") (pintype "bidirectional"))
      (node (ref "U1") (pin "P$4") (pinfunction "PC15-OSC32_OUT_P$4") (pintype "bidirectional"))
      (node (ref "U1") (pin "P$41") (pinfunction "PB5_P$41") (pintype "bidirectional"))
      (node (ref "U1") (pin "P$42") (pinfunction "PB6_P$42") (pintype "bidirectional"))
      (node (ref "U1") (pin "P$43") (pinfunction "PB7_P$43") (pintype "bidirectional"))
      (node (ref "U1") (pin "P$47") (pinfunction "VSS_2_P$47") (pintype "power_in"))
      (node (ref "X1") (pin "P$2") (pinfunction "2_P$2") (pintype "passive"))
    )
    (net (code "5") (name "Net-(AOA-K)") (class "Default")
      (node (ref "AO") (pin "1") (pinfunction "K_1") (pintype "passive"))
      (node (ref "C28") (pin "2") (pinfunction "2_2") (pintype "passive"))
      (node (ref "C29") (pin "2") (pinfunction "2_2") (pintype "passive"))
      (node (ref "U2") (pin "26") (pinfunction "IOUT_26") (pintype "output"))
      (node (ref "U2") (pin "32") (pinfunction "VOUT_32") (pintype "output"))
      (node (ref "U3") (pin "3") (pinfunction "IN+_3") (pintype "input"))
    )
    (net (code "6") (name "Net-(D1-PadA)") (class "Default")
      (node (ref "D1") (pin "A") (pinfunction "A_A") (pintype "passive"))
      (node (ref "R1") (pin "1") (pinfunction "1_1") (pintype "passive"))
    )
    (net (code "7") (name "Net-(U1-NRST)") (class "Default")
      (node (ref "C8") (pin "1") (pinfunction "1_1") (pintype "passive"))
      (node (ref "R") (pin "P$1") (pinfunction "P$1_P$1") (pintype "passive"))
      (node (ref "R") (pin "P$2") (pinfunction "P$1_P$2") (pintype "passive"))
      (node (ref "U1") (pin "P$7") (pinfunction "NRST_P$7") (pintype "passive"))
    )
    (net (code "8") (name "Net-(U1-PA11)") (class "Default")
      (node (ref "R1") (pin "2") (pinfunction "2_2") (pintype "passive"))
      (node (ref "U1") (pin "P$32") (pinfunction "PA11_P$32") (pintype "bidirectional"))
    )
    (net (code "9") (name "Net-(U1-PA13)") (class "Default")
      (node (ref "D") (pin "P$1") (pinfunction "P$1_P$1") (pintype "passive"))
      (node (ref "D") (pin "P$2") (pinfunction "P$1_P$2") (pintype "passive"))
      (node (ref "U1") (pin "P$34") (pinfunction "PA13_P$34") (pintype "bidirectional"))
    )
    (net (code "10") (name "Net-(U1-PA14)") (class "Default")
      (node (ref "C") (pin "P$1") (pinfunction "P$1_P$1") (pintype "passive"))
      (node (ref "C") (pin "P$2") (pinfunction "P$1_P$2") (pintype "passive"))
      (node (ref "U1") (pin "P$37") (pinfunction "PA14_P$37") (pintype "bidirectional"))
    )
    (net (code "11") (name "Net-(U1-PF0-OSC_IN)") (class "Default")
      (node (ref "U1") (pin "P$5") (pinfunction "PF0-OSC_IN_P$5") (pintype "bidirectional"))
      (node (ref "X1") (pin "P$1") (pinfunction "1_P$1") (pintype "passive"))
    )
    (net (code "12") (name "Net-(U1-PF1-OSC_OUT)") (class "Default")
      (node (ref "U1") (pin "P$6") (pinfunction "PF1-OSC_OUT_P$6") (pintype "bidirectional"))
      (node (ref "X1") (pin "P$3") (pinfunction "3_P$3") (pintype "passive"))
    )
    (net (code "13") (name "Net-(U1-PF11-OSC_BOOT0)") (class "Default")
      (node (ref "B") (pin "P$1") (pinfunction "P$1_P$1") (pintype "passive"))
      (node (ref "B") (pin "P$2") (pinfunction "P$1_P$2") (pintype "passive"))
      (node (ref "R3") (pin "2") (pinfunction "2_2") (pintype "passive"))
      (node (ref "U1") (pin "P$44") (pinfunction "PF11-OSC_BOOT0_P$44") (pintype "bidirectional"))
    )
    (net (code "14") (name "Net-(U2-+VSENSE)") (class "Default")
      (node (ref "U2") (pin "33") (pinfunction "+VSENSE_33") (pintype "input"))
      (node (ref "U3") (pin "1") (pinfunction "OUT_1") (pintype "output"))
      (node (ref "U3") (pin "4") (pinfunction "IN-_4") (pintype "input"))
    )
    (net (code "15") (name "Net-(U2-CAP1)") (class "Default")
      (node (ref "C27") (pin "1") (pinfunction "1_1") (pintype "passive"))
      (node (ref "U2") (pin "28") (pinfunction "CAP1_28") (pintype "input"))
    )
    (net (code "16") (name "Net-(U2-CAP2)") (class "Default")
      (node (ref "C26") (pin "1") (pinfunction "1_1") (pintype "passive"))
      (node (ref "U2") (pin "29") (pinfunction "CAP2_29") (pintype "input"))
    )
    (net (code "17") (name "Net-(U2-CMP)") (class "Default")
      (node (ref "C28") (pin "1") (pinfunction "1_1") (pintype "passive"))
      (node (ref "U2") (pin "24") (pinfunction "CMP_24") (pintype "input"))
    )
    (net (code "18") (name "Net-(U2-HART-IN)") (class "Default")
      (node (ref "C30") (pin "1") (pinfunction "1_1") (pintype "passive"))
      (node (ref "U2") (pin "25") (pinfunction "HART-IN_25") (pintype "input"))
    )
    (net (code "19") (name "Net-(U2-REFIN)") (class "Default")
      (node (ref "C19") (pin "1") (pinfunction "1_1") (pintype "passive"))
      (node (ref "U2") (pin "17") (pinfunction "REFOUT_17") (pintype "output"))
      (node (ref "U2") (pin "18") (pinfunction "REFIN_18") (pintype "input"))
    )
    (net (code "20") (name "SPI2_CS") (class "Default")
      (node (ref "U1") (pin "P$25") (pinfunction "PB12_P$25") (pintype "bidirectional"))
      (node (ref "U2") (pin "6") (pinfunction "LATCH_6") (pintype "input"))
    )
    (net (code "21") (name "SPI2_MISO") (class "Default")
      (node (ref "U1") (pin "P$27") (pinfunction "PB14_P$27") (pintype "bidirectional"))
      (node (ref "U2") (pin "9") (pinfunction "SDO_9") (pintype "output"))
    )
    (net (code "22") (name "SPI2_MOSI") (class "Default")
      (node (ref "U1") (pin "P$28") (pinfunction "PB15_P$28") (pintype "bidirectional"))
      (node (ref "U2") (pin "8") (pinfunction "DIN_8") (pintype "input"))
    )
    (net (code "23") (name "SPI2_SCK") (class "Default")
      (node (ref "U1") (pin "P$26") (pinfunction "PB13_P$26") (pintype "bidirectional"))
      (node (ref "U2") (pin "7") (pinfunction "SCLK_7") (pintype "input"))
    )
    (net (code "24") (name "UART1_RX*") (class "Default")
      (node (ref "P1") (pin "PAD_PD5") (pinfunction "SD5_PAD_PD5") (pintype "bidirectional"))
      (node (ref "U1") (pin "P$31") (pinfunction "PA10_P$31") (pintype "bidirectional"))
    )
    (net (code "25") (name "UART1_TX*") (class "Default")
      (node (ref "P1") (pin "PAD_PU5") (pinfunction "SU5_PAD_PU5") (pintype "bidirectional"))
      (node (ref "U1") (pin "P$30") (pinfunction "PA9_P$30") (pintype "bidirectional"))
    )
    (net (code "26") (name "UART2_RX*") (class "Default")
      (node (ref "P1") (pin "PAD_PD2") (pinfunction "SD2_PAD_PD2") (pintype "bidirectional"))
      (node (ref "U1") (pin "P$13") (pinfunction "PA3_P$13") (pintype "bidirectional"))
    )
    (net (code "27") (name "UART2_TX*") (class "Default")
      (node (ref "P1") (pin "PAD_PU2") (pinfunction "SU2_PAD_PU2") (pintype "bidirectional"))
      (node (ref "U1") (pin "P$12") (pinfunction "PA2_P$12") (pintype "bidirectional"))
    )
    (net (code "28") (name "UART3_RX") (class "Default")
      (node (ref "P1") (pin "PAD_PD4") (pinfunction "SD4_PAD_PD4") (pintype "bidirectional"))
      (node (ref "U1") (pin "P$22") (pinfunction "PB11_P$22") (pintype "bidirectional"))
    )
    (net (code "29") (name "UART3_TX") (class "Default")
      (node (ref "P1") (pin "PAD_PU4") (pinfunction "SU4_PAD_PU4") (pintype "bidirectional"))
      (node (ref "U1") (pin "P$21") (pinfunction "PB10_P$21") (pintype "bidirectional"))
    )
    (net (code "30") (name "UART4_RX") (class "Default")
      (node (ref "U1") (pin "P$11") (pinfunction "PA1_P$11") (pintype "bidirectional"))
    )
    (net (code "31") (name "UART4_TX") (class "Default")
      (node (ref "U1") (pin "P$10") (pinfunction "PA0_P$10") (pintype "bidirectional"))
    )
    (net (code "32") (name "UART5_RX") (class "Default")
      (node (ref "P1") (pin "PAD_PD1") (pinfunction "SD1_PAD_PD1") (pintype "bidirectional"))
      (node (ref "U1") (pin "P$40") (pinfunction "PB4_P$40") (pintype "bidirectional"))
    )
    (net (code "33") (name "UART5_TX") (class "Default")
      (node (ref "P1") (pin "PAD_PU1") (pinfunction "SU1_PAD_PU1") (pintype "bidirectional"))
      (node (ref "U1") (pin "P$39") (pinfunction "PB3_P$39") (pintype "bidirectional"))
    )
    (net (code "34") (name "UART6_RX") (class "Default")
      (node (ref "U1") (pin "P$15") (pinfunction "PA5_P$15") (pintype "bidirectional"))
    )
    (net (code "35") (name "UART6_TX") (class "Default")
      (node (ref "U1") (pin "P$14") (pinfunction "PA4_P$14") (pintype "bidirectional"))
    )
    (net (code "36") (name "VDD") (class "Default")
      (node (ref "C3") (pin "1") (pinfunction "1_1") (pintype "passive"))
      (node (ref "C4") (pin "1") (pinfunction "+_1") (pintype "passive"))
      (node (ref "C5") (pin "1") (pinfunction "1_1") (pintype "passive"))
      (node (ref "C6") (pin "1") (pinfunction "1_1") (pintype "passive"))
      (node (ref "C7") (pin "1") (pinfunction "+_1") (pintype "passive"))
      (node (ref "C9") (pin "1") (pinfunction "1_1") (pintype "passive"))
      (node (ref "FB1") (pin "2") (pinfunction "2_2") (pintype "passive"))
      (node (ref "P1") (pin "PAD_PU10") (pinfunction "VDD4_PAD_PU10") (pintype "power_in"))
      (node (ref "P1") (pin "PAD_PU11") (pinfunction "VDD5_PAD_PU11") (pintype "power_in"))
      (node (ref "P1") (pin "PAD_PU12") (pinfunction "VDD6_PAD_PU12") (pintype "power_in"))
      (node (ref "P1") (pin "PAD_PU7") (pinfunction "VDD1_PAD_PU7") (pintype "power_in"))
      (node (ref "P1") (pin "PAD_PU8") (pinfunction "VDD2_PAD_PU8") (pintype "power_in"))
      (node (ref "P1") (pin "PAD_PU9") (pinfunction "VDD3_PAD_PU9") (pintype "power_in"))
      (node (ref "U1") (pin "P$1") (pinfunction "VBAT_P$1") (pintype "power_in"))
      (node (ref "U1") (pin "P$24") (pinfunction "VDD_0_P$24") (pintype "power_in"))
      (node (ref "U1") (pin "P$36") (pinfunction "VDDIO2_P$36") (pintype "power_in"))
      (node (ref "U1") (pin "P$48") (pinfunction "VDD_1_P$48") (pintype "power_in"))
    )
    (net (code "37") (name "VDDA") (class "Default")
      (node (ref "C1") (pin "1") (pinfunction "1_1") (pintype "passive"))
      (node (ref "C18") (pin "1") (pinfunction "1_1") (pintype "passive"))
      (node (ref "C2") (pin "1") (pinfunction "+_1") (pintype "passive"))
      (node (ref "FB1") (pin "1") (pinfunction "1_1") (pintype "passive"))
      (node (ref "R5") (pin "2") (pinfunction "2_2") (pintype "passive"))
      (node (ref "U1") (pin "P$9") (pinfunction "VDDA_P$9") (pintype "power_in"))
      (node (ref "U2") (pin "39") (pinfunction "DVDD_39") (pintype "power_in"))
    )
    (net (code "38") (name "VSSA") (class "Default")
      (node (ref "AO") (pin "2") (pinfunction "K_2") (pintype "passive"))
      (node (ref "C1") (pin "2") (pinfunction "2_2") (pintype "passive"))
      (node (ref "C12") (pin "-") (pinfunction "-_-") (pintype "passive"))
      (node (ref "C13") (pin "2") (pinfunction "2_2") (pintype "passive"))
      (node (ref "C14") (pin "2") (pinfunction "2_2") (pintype "passive"))
      (node (ref "C15") (pin "+") (pinfunction "+_+") (pintype "passive"))
      (node (ref "C16") (pin "2") (pinfunction "2_2") (pintype "passive"))
      (node (ref "C17") (pin "2") (pinfunction "2_2") (pintype "passive"))
      (node (ref "C18") (pin "2") (pinfunction "2_2") (pintype "passive"))
      (node (ref "C19") (pin "2") (pinfunction "2_2") (pintype "passive"))
      (node (ref "C2") (pin "2") (pinfunction "-_2") (pintype "passive"))
      (node (ref "C20") (pin "2") (pinfunction "2_2") (pintype "passive"))
      (node (ref "C21") (pin "2") (pinfunction "2_2") (pintype "passive"))
      (node (ref "C22") (pin "2") (pinfunction "2_2") (pintype "passive"))
      (node (ref "C23") (pin "2") (pinfunction "2_2") (pintype "passive"))
      (node (ref "C24") (pin "2") (pinfunction "2_2") (pintype "passive"))
      (node (ref "C25") (pin "2") (pinfunction "2_2") (pintype "passive"))
      (node (ref "C29") (pin "1") (pinfunction "1_1") (pintype "passive"))
      (node (ref "C30") (pin "2") (pinfunction "2_2") (pintype "passive"))
      (node (ref "C31") (pin "2") (pinfunction "2_2") (pintype "passive"))
      (node (ref "C32") (pin "2") (pinfunction "2_2") (pintype "passive"))
      (node (ref "C33") (pin "2") (pinfunction "2_2") (pintype "passive"))
      (node (ref "C34") (pin "2") (pinfunction "2_2") (pintype "passive"))
      (node (ref "PWR") (pin "2") (pinfunction "K_2") (pintype "passive"))
      (node (ref "R2") (pin "2") (pinfunction "2_2") (pintype "passive"))
      (node (ref "U1") (pin "P$8") (pinfunction "VSS_A_P$8") (pintype "power_in"))
      (node (ref "U2") (pin "12") (pinfunction "GND_3_12") (pintype "power_in"))
      (node (ref "U2") (pin "13") (pinfunction "GND_4_13") (pintype "power_in"))
      (node (ref "U2") (pin "15") (pinfunction "GND_15") (pintype "power_in"))
      (node (ref "U2") (pin "23") (pinfunction "DVDD-EN_23") (pintype "input"))
      (node (ref "U2") (pin "3") (pinfunction "GND_2_3") (pintype "power_in"))
      (node (ref "U2") (pin "34") (pinfunction "-VSENSE_34") (pintype "input"))
      (node (ref "U2") (pin "4") (pinfunction "CLR-SEL_4") (pintype "input"))
      (node (ref "U2") (pin "5") (pinfunction "CLR_5") (pintype "input"))
    )
    (net (code "39") (name "unconnected-(U1-PA12-PadP$33)") (class "Default")
      (node (ref "U1") (pin "P$33") (pinfunction "PA12_P$33") (pintype "bidirectional"))
    )
    (net (code "40") (name "unconnected-(U1-PB8-PadP$45)") (class "Default")
      (node (ref "U1") (pin "P$45") (pinfunction "PB8_P$45") (pintype "bidirectional"))
    )
    (net (code "41") (name "unconnected-(U1-PB9-PadP$46)") (class "Default")
      (node (ref "U1") (pin "P$46") (pinfunction "PB9_P$46") (pintype "bidirectional"))
    )
    (net (code "42") (name "unconnected-(U2-BOOST-Pad27)") (class "Default")
      (node (ref "U2") (pin "27") (pinfunction "BOOST_27") (pintype "output"))
    )
    (net (code "43") (name "unconnected-(U2-ISET-R-Pad16)") (class "Default")
      (node (ref "U2") (pin "16") (pinfunction "ISET-R_16") (pintype "input"))
    )
    (net (code "44") (name "unconnected-(U2-NC-Pad40)") (class "Default")
      (node (ref "U2") (pin "40") (pinfunction "NC_40") (pintype "passive"))
    )
    (net (code "45") (name "unconnected-(U2-NC_2-Pad1)") (class "Default")
      (node (ref "U2") (pin "1") (pinfunction "NC_2_1") (pintype "passive"))
    )
    (net (code "46") (name "unconnected-(U2-NC_3-Pad10)") (class "Default")
      (node (ref "U2") (pin "10") (pinfunction "NC_3_10") (pintype "passive"))
    )
    (net (code "47") (name "unconnected-(U2-NC_4-Pad11)") (class "Default")
      (node (ref "U2") (pin "11") (pinfunction "NC_4_11") (pintype "passive"))
    )
    (net (code "48") (name "unconnected-(U2-NC_5-Pad19)") (class "Default")
      (node (ref "U2") (pin "19") (pinfunction "NC_5_19") (pintype "passive"))
    )
    (net (code "49") (name "unconnected-(U2-NC_6-Pad20)") (class "Default")
      (node (ref "U2") (pin "20") (pinfunction "NC_6_20") (pintype "passive"))
    )
    (net (code "50") (name "unconnected-(U2-NC_7-Pad21)") (class "Default")
      (node (ref "U2") (pin "21") (pinfunction "NC_7_21") (pintype "passive"))
    )
    (net (code "51") (name "unconnected-(U2-NC_8-Pad22)") (class "Default")
      (node (ref "U2") (pin "22") (pinfunction "NC_8_22") (pintype "passive"))
    )
    (net (code "52") (name "unconnected-(U2-NC_9-Pad30)") (class "Default")
      (node (ref "U2") (pin "30") (pinfunction "NC_9_30") (pintype "passive"))
    )
    (net (code "53") (name "unconnected-(U2-NC_10-Pad31)") (class "Default")
      (node (ref "U2") (pin "31") (pinfunction "NC_10_31") (pintype "passive"))
    )
    (net (code "54") (name "unconnected-(U2-NC_11-Pad35)") (class "Default")
      (node (ref "U2") (pin "35") (pinfunction "NC_11_35") (pintype "passive"))
    )
    (net (code "55") (name "unconnected-(U2-NC_12-Pad38)") (class "Default")
      (node (ref "U2") (pin "38") (pinfunction "NC_12_38") (pintype "passive"))
    )
  )
)
